# lipol_source.net
KiCad netlist of a schematic drawn in EAGLE
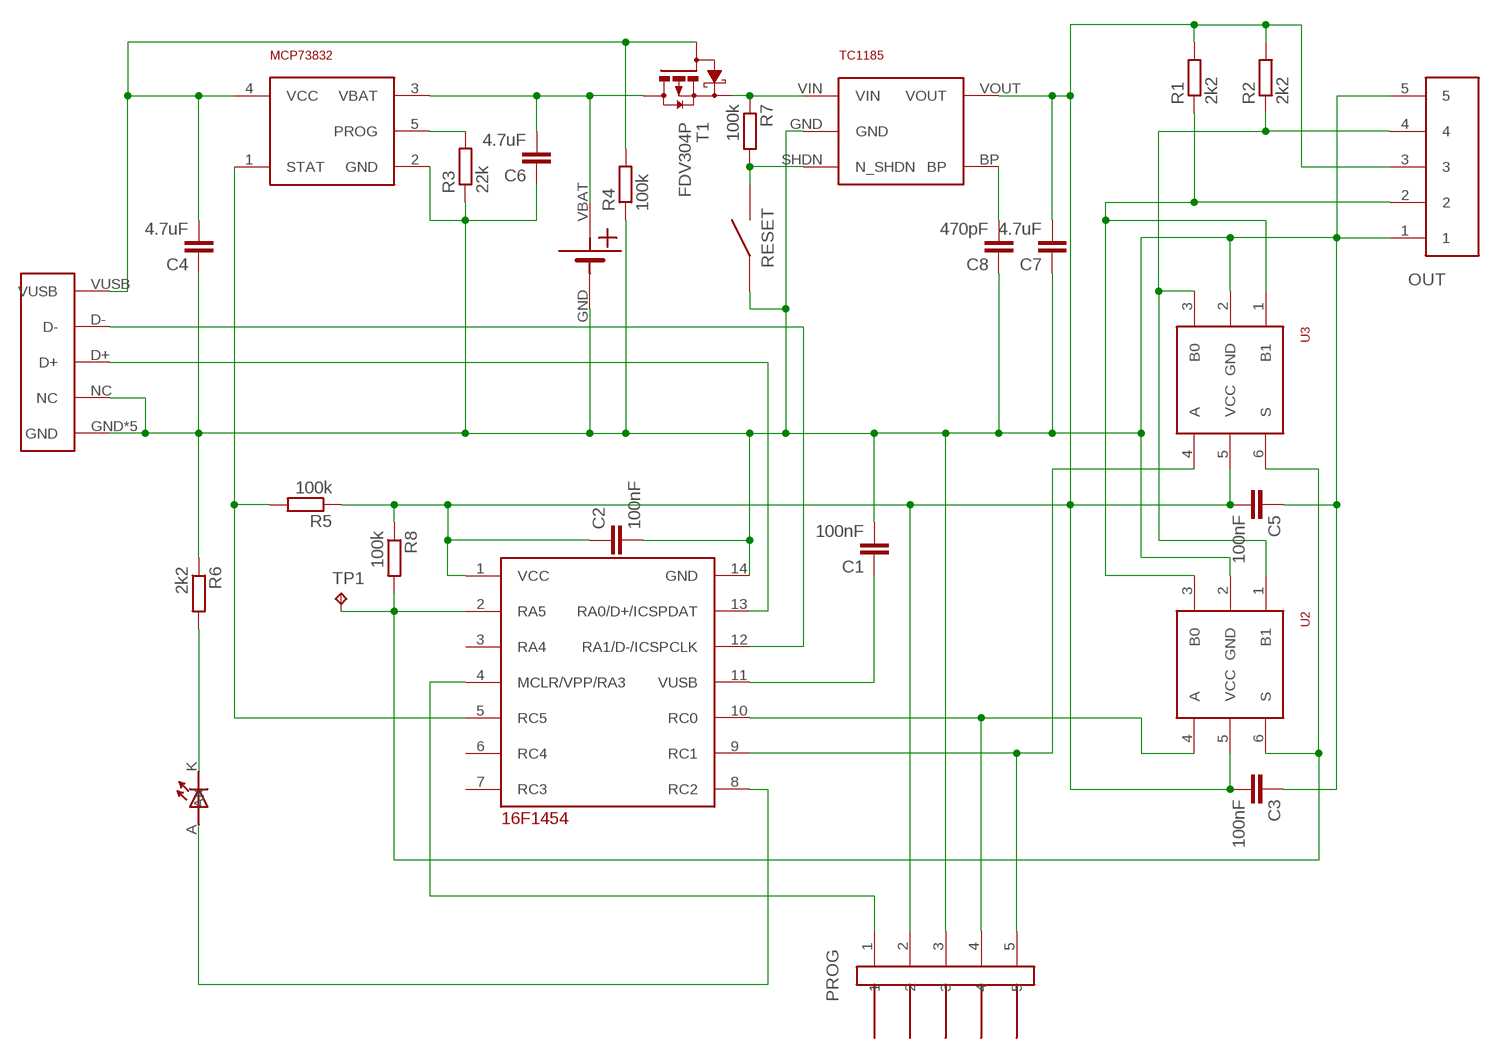
[diagram p0: schematic, sheet 1]

(export (version "E")
  (design (tool "Eeschema 10.0.6"))
  (components
    (comp (ref "C1")
      (value "100nF")
      (footprint "eagle-import:C0603K")
      (libsource (lib "eagle-import") (part "C-EUC0603K"))
    )
    (comp (ref "C2")
      (value "100nF")
      (footprint "eagle-import:C0603K")
      (libsource (lib "eagle-import") (part "C-EUC0603K"))
    )
    (comp (ref "C3")
      (value "100nF")
      (footprint "eagle-import:C0603K")
      (libsource (lib "eagle-import") (part "C-EUC0603K"))
    )
    (comp (ref "C4")
      (value "4.7uF")
      (footprint "eagle-import:C0603K")
      (libsource (lib "eagle-import") (part "C-EUC0603K"))
    )
    (comp (ref "C5")
      (value "100nF")
      (footprint "eagle-import:C0603K")
      (libsource (lib "eagle-import") (part "C-EUC0603K"))
    )
    (comp (ref "C6")
      (value "4.7uF")
      (footprint "eagle-import:C0603K")
      (libsource (lib "eagle-import") (part "C-EUC0603K"))
    )
    (comp (ref "C7")
      (value "4.7uF")
      (footprint "eagle-import:C0603K")
      (libsource (lib "eagle-import") (part "C-EUC0603K"))
    )
    (comp (ref "C8")
      (value "470pF")
      (footprint "eagle-import:C0603K")
      (libsource (lib "eagle-import") (part "C-EUC0603K"))
    )
    (comp (ref "D1")
      (value "LED1.8")
      (footprint "eagle-import:LED1.8")
      (libsource (lib "eagle-import") (part "LED1.8"))
    )
    (comp (ref "MCP73832")
      (value "MCP73831")
      (footprint "eagle-import:SOT23-5")
      (libsource (lib "eagle-import") (part "MCP73831"))
    )
    (comp (ref "OUT")
      (value "JUMPER5F-90")
      (footprint "eagle-import:JUMPER5F-90")
      (libsource (lib "eagle-import") (part "JUMPER5F-90"))
    )
    (comp (ref "PROG")
      (value "JUMPER5M")
      (footprint "eagle-import:JUMPER5M")
      (libsource (lib "eagle-import") (part "JUMPER5M"))
    )
    (comp (ref "R1")
      (value "2k2")
      (footprint "eagle-import:R0603")
      (libsource (lib "eagle-import") (part "R-EU_R0603"))
    )
    (comp (ref "R2")
      (value "2k2")
      (footprint "eagle-import:R0603")
      (libsource (lib "eagle-import") (part "R-EU_R0603"))
    )
    (comp (ref "R3")
      (value "22k")
      (footprint "eagle-import:R0603")
      (libsource (lib "eagle-import") (part "R-EU_R0603"))
    )
    (comp (ref "R4")
      (value "100k")
      (footprint "eagle-import:R0603")
      (libsource (lib "eagle-import") (part "R-EU_R0603"))
    )
    (comp (ref "R5")
      (value "100k")
      (footprint "eagle-import:R0603")
      (libsource (lib "eagle-import") (part "R-EU_R0603"))
    )
    (comp (ref "R6")
      (value "2k2")
      (footprint "eagle-import:R0603")
      (libsource (lib "eagle-import") (part "R-EU_R0603"))
    )
    (comp (ref "R7")
      (value "100k")
      (footprint "eagle-import:R0603")
      (libsource (lib "eagle-import") (part "R-EU_R0603"))
    )
    (comp (ref "R8")
      (value "100k")
      (footprint "eagle-import:R0603")
      (libsource (lib "eagle-import") (part "R-EU_R0603"))
    )
    (comp (ref "RESET")
      (value "BYTTON-B3U")
      (footprint "eagle-import:BUTTON-B3U")
      (libsource (lib "eagle-import") (part "BYTTON-B3U"))
    )
    (comp (ref "T1")
      (value "FDV304P")
      (footprint "eagle-import:SOT23")
      (libsource (lib "eagle-import") (part "P-MOSFET-FDV304P"))
    )
    (comp (ref "TC1185")
      (value "STABILISER_APE8865")
      (footprint "eagle-import:SOT32-5")
      (libsource (lib "eagle-import") (part "STABILISER_APE8865"))
    )
    (comp (ref "TP1")
      (value "TPB1,27")
      (footprint "eagle-import:B1,27")
      (libsource (lib "eagle-import") (part "TPB1,27"))
    )
    (comp (ref "U$3")
      (value "LIPOL_21X17")
      (footprint "eagle-import:LIPOL_21X17")
      (libsource (lib "eagle-import") (part "LIPOL_21X17"))
    )
    (comp (ref "U1")
      (value "16F1454")
      (footprint "eagle-import:TSSOP14")
      (libsource (lib "eagle-import") (part "16F1454"))
    )
    (comp (ref "U2")
      (value "NC7SB3157P6X")
      (footprint "eagle-import:SC70-6L")
      (libsource (lib "eagle-import") (part "NC7SB3157P6X"))
    )
    (comp (ref "U3")
      (value "NC7SB3157P6X")
      (footprint "eagle-import:SC70-6L")
      (libsource (lib "eagle-import") (part "NC7SB3157P6X"))
    )
    (comp (ref "USB")
      (value "USBMICRO")
      (footprint "eagle-import:MICROUSB-MOLEX")
      (libsource (lib "eagle-import") (part "USBMICRO"))
    )
  )
  (nets
    (net (code "1") (name "Net-(C8-Pad2)") (class "Default")
      (node (ref "C8") (pin "2") (pinfunction "2_2") (pintype "passive"))
      (node (ref "TC1185") (pin "BP") (pinfunction "BP_BP") (pintype "bidirectional"))
    )
    (net (code "2") (name "Net-(D1-PadK)") (class "Default")
      (node (ref "D1") (pin "K") (pinfunction "K_K") (pintype "bidirectional"))
      (node (ref "R6") (pin "2") (pinfunction "2_2") (pintype "passive"))
    )
    (net (code "3") (name "Net-(MCP73832-GND)") (class "Default")
      (node (ref "C1") (pin "2") (pinfunction "2_2") (pintype "passive"))
      (node (ref "C2") (pin "2") (pinfunction "2_2") (pintype "passive"))
      (node (ref "C3") (pin "1") (pinfunction "1_1") (pintype "passive"))
      (node (ref "C4") (pin "1") (pinfunction "1_1") (pintype "passive"))
      (node (ref "C5") (pin "1") (pinfunction "1_1") (pintype "passive"))
      (node (ref "C6") (pin "1") (pinfunction "1_1") (pintype "passive"))
      (node (ref "C7") (pin "1") (pinfunction "1_1") (pintype "passive"))
      (node (ref "C8") (pin "1") (pinfunction "1_1") (pintype "passive"))
      (node (ref "MCP73832") (pin "2") (pinfunction "GND_2") (pintype "bidirectional"))
      (node (ref "OUT") (pin "1") (pinfunction "1_1") (pintype "bidirectional"))
      (node (ref "OUT") (pin "5") (pinfunction "5_5") (pintype "bidirectional"))
      (node (ref "PROG") (pin "3") (pinfunction "3_3") (pintype "bidirectional"))
      (node (ref "R3") (pin "1") (pinfunction "1_1") (pintype "passive"))
      (node (ref "R4") (pin "1") (pinfunction "1_1") (pintype "passive"))
      (node (ref "R6") (pin "1") (pinfunction "1_1") (pintype "passive"))
      (node (ref "RESET") (pin "P$1") (pinfunction "P$1_P$1") (pintype "bidirectional"))
      (node (ref "TC1185") (pin "GND") (pinfunction "GND_GND") (pintype "bidirectional"))
      (node (ref "U$3") (pin "GND") (pinfunction "GND_GND") (pintype "power_in"))
      (node (ref "U1") (pin "14") (pinfunction "GND_14") (pintype "power_in"))
      (node (ref "U2") (pin "2") (pinfunction "GND_2") (pintype "power_in"))
      (node (ref "U3") (pin "2") (pinfunction "GND_2") (pintype "power_in"))
      (node (ref "USB") (pin "GND") (pinfunction "GND_GND") (pintype "bidirectional"))
      (node (ref "USB") (pin "NC") (pinfunction "NC_NC") (pintype "bidirectional"))
      (node (ref "USB") (pin "P$1") (pinfunction "GND_P$1") (pintype "bidirectional"))
      (node (ref "USB") (pin "P$2") (pinfunction "GND_P$2") (pintype "bidirectional"))
      (node (ref "USB") (pin "P$3") (pinfunction "GND_P$3") (pintype "bidirectional"))
      (node (ref "USB") (pin "P$6") (pinfunction "GND_P$6") (pintype "bidirectional"))
    )
    (net (code "4") (name "Net-(MCP73832-PROG)") (class "Default")
      (node (ref "MCP73832") (pin "5") (pinfunction "PROG_5") (pintype "bidirectional"))
      (node (ref "R3") (pin "2") (pinfunction "2_2") (pintype "passive"))
    )
    (net (code "5") (name "Net-(MCP73832-STAT)") (class "Default")
      (node (ref "MCP73832") (pin "1") (pinfunction "STAT_1") (pintype "bidirectional"))
      (node (ref "R5") (pin "2") (pinfunction "2_2") (pintype "passive"))
      (node (ref "U1") (pin "5") (pinfunction "RC5_5") (pintype "bidirectional"))
    )
    (net (code "6") (name "Net-(MCP73832-VBAT)") (class "Default")
      (node (ref "C6") (pin "2") (pinfunction "2_2") (pintype "passive"))
      (node (ref "MCP73832") (pin "3") (pinfunction "VBAT_3") (pintype "bidirectional"))
      (node (ref "T1") (pin "D") (pinfunction "D_D") (pintype "passive"))
      (node (ref "U$3") (pin "VBAT") (pinfunction "VBAT_VBAT") (pintype "power_in"))
    )
    (net (code "7") (name "Net-(MCP73832-VCC)") (class "Default")
      (node (ref "C4") (pin "2") (pinfunction "2_2") (pintype "passive"))
      (node (ref "MCP73832") (pin "4") (pinfunction "VCC_4") (pintype "bidirectional"))
      (node (ref "R4") (pin "2") (pinfunction "2_2") (pintype "passive"))
      (node (ref "T1") (pin "G") (pinfunction "G_G") (pintype "passive"))
      (node (ref "USB") (pin "VUSB") (pinfunction "VUSB_VUSB") (pintype "bidirectional"))
    )
    (net (code "8") (name "Net-(R7-Pad1)") (class "Default")
      (node (ref "R7") (pin "1") (pinfunction "1_1") (pintype "passive"))
      (node (ref "T1") (pin "S") (pinfunction "S_S") (pintype "passive"))
      (node (ref "TC1185") (pin "VIN") (pinfunction "VIN_VIN") (pintype "bidirectional"))
    )
    (net (code "9") (name "Net-(TC1185-N_SHDN)") (class "Default")
      (node (ref "R7") (pin "2") (pinfunction "2_2") (pintype "passive"))
      (node (ref "RESET") (pin "P$2") (pinfunction "P$2_P$2") (pintype "bidirectional"))
      (node (ref "TC1185") (pin "SHDN") (pinfunction "N_SHDN_SHDN") (pintype "bidirectional"))
    )
    (net (code "10") (name "Net-(U1-MCLR{slash}VPP{slash}RA3)") (class "Default")
      (node (ref "PROG") (pin "1") (pinfunction "1_1") (pintype "bidirectional"))
      (node (ref "U1") (pin "4") (pinfunction "MCLR/VPP/RA3_4") (pintype "bidirectional"))
    )
    (net (code "11") (name "Net-(U1-RA0{slash}D+{slash}ICSPDAT)") (class "Default")
      (node (ref "U1") (pin "13") (pinfunction "RA0/D+/ICSPDAT_13") (pintype "bidirectional"))
      (node (ref "USB") (pin "D+") (pinfunction "D+_D+") (pintype "bidirectional"))
    )
    (net (code "12") (name "Net-(U1-RA1{slash}D-{slash}ICSPCLK)") (class "Default")
      (node (ref "U1") (pin "12") (pinfunction "RA1/D-/ICSPCLK_12") (pintype "bidirectional"))
      (node (ref "USB") (pin "D-") (pinfunction "D-_D-") (pintype "bidirectional"))
    )
    (net (code "13") (name "Net-(U1-RA5)") (class "Default")
      (node (ref "R8") (pin "2") (pinfunction "2_2") (pintype "passive"))
      (node (ref "TP1") (pin "TP") (pinfunction "TP_TP") (pintype "input"))
      (node (ref "U1") (pin "2") (pinfunction "RA5_2") (pintype "bidirectional"))
      (node (ref "U2") (pin "6") (pinfunction "S_6") (pintype "bidirectional"))
      (node (ref "U3") (pin "6") (pinfunction "S_6") (pintype "bidirectional"))
    )
    (net (code "14") (name "Net-(U1-RC0)") (class "Default")
      (node (ref "PROG") (pin "4") (pinfunction "4_4") (pintype "bidirectional"))
      (node (ref "U1") (pin "10") (pinfunction "RC0_10") (pintype "bidirectional"))
      (node (ref "U2") (pin "4") (pinfunction "A_4") (pintype "bidirectional"))
    )
    (net (code "15") (name "Net-(U1-RC1)") (class "Default")
      (node (ref "PROG") (pin "5") (pinfunction "5_5") (pintype "bidirectional"))
      (node (ref "U1") (pin "9") (pinfunction "RC1_9") (pintype "bidirectional"))
      (node (ref "U3") (pin "4") (pinfunction "A_4") (pintype "bidirectional"))
    )
    (net (code "16") (name "Net-(U1-RC2)") (class "Default")
      (node (ref "D1") (pin "A") (pinfunction "A_A") (pintype "bidirectional"))
      (node (ref "U1") (pin "8") (pinfunction "RC2_8") (pintype "bidirectional"))
    )
    (net (code "17") (name "Net-(U1-VCC)") (class "Default")
      (node (ref "C2") (pin "1") (pinfunction "1_1") (pintype "passive"))
      (node (ref "C3") (pin "2") (pinfunction "2_2") (pintype "passive"))
      (node (ref "C5") (pin "2") (pinfunction "2_2") (pintype "passive"))
      (node (ref "C7") (pin "2") (pinfunction "2_2") (pintype "passive"))
      (node (ref "OUT") (pin "3") (pinfunction "3_3") (pintype "bidirectional"))
      (node (ref "PROG") (pin "2") (pinfunction "2_2") (pintype "bidirectional"))
      (node (ref "R1") (pin "2") (pinfunction "2_2") (pintype "passive"))
      (node (ref "R2") (pin "2") (pinfunction "2_2") (pintype "passive"))
      (node (ref "R5") (pin "1") (pinfunction "1_1") (pintype "passive"))
      (node (ref "R8") (pin "1") (pinfunction "1_1") (pintype "passive"))
      (node (ref "TC1185") (pin "VOUT") (pinfunction "VOUT_VOUT") (pintype "bidirectional"))
      (node (ref "U1") (pin "1") (pinfunction "VCC_1") (pintype "power_in"))
      (node (ref "U2") (pin "5") (pinfunction "VCC_5") (pintype "power_in"))
      (node (ref "U3") (pin "5") (pinfunction "VCC_5") (pintype "power_in"))
    )
    (net (code "18") (name "Net-(U1-VUSB)") (class "Default")
      (node (ref "C1") (pin "1") (pinfunction "1_1") (pintype "passive"))
      (node (ref "U1") (pin "11") (pinfunction "VUSB_11") (pintype "bidirectional"))
    )
    (net (code "19") (name "Net-(U2-B0)") (class "Default")
      (node (ref "OUT") (pin "2") (pinfunction "2_2") (pintype "bidirectional"))
      (node (ref "R1") (pin "1") (pinfunction "1_1") (pintype "passive"))
      (node (ref "U2") (pin "3") (pinfunction "B0_3") (pintype "bidirectional"))
      (node (ref "U3") (pin "1") (pinfunction "B1_1") (pintype "bidirectional"))
    )
    (net (code "20") (name "Net-(U2-B1)") (class "Default")
      (node (ref "OUT") (pin "4") (pinfunction "4_4") (pintype "bidirectional"))
      (node (ref "R2") (pin "1") (pinfunction "1_1") (pintype "passive"))
      (node (ref "U2") (pin "1") (pinfunction "B1_1") (pintype "bidirectional"))
      (node (ref "U3") (pin "3") (pinfunction "B0_3") (pintype "bidirectional"))
    )
    (net (code "21") (name "unconnected-(U1-RA4-Pad3)") (class "Default")
      (node (ref "U1") (pin "3") (pinfunction "RA4_3") (pintype "bidirectional"))
    )
    (net (code "22") (name "unconnected-(U1-RC3-Pad7)") (class "Default")
      (node (ref "U1") (pin "7") (pinfunction "RC3_7") (pintype "bidirectional"))
    )
    (net (code "23") (name "unconnected-(U1-RC4-Pad6)") (class "Default")
      (node (ref "U1") (pin "6") (pinfunction "RC4_6") (pintype "bidirectional"))
    )
  )
)
